# tiny-tinyisp.net
KiCad netlist of a schematic drawn in EAGLE
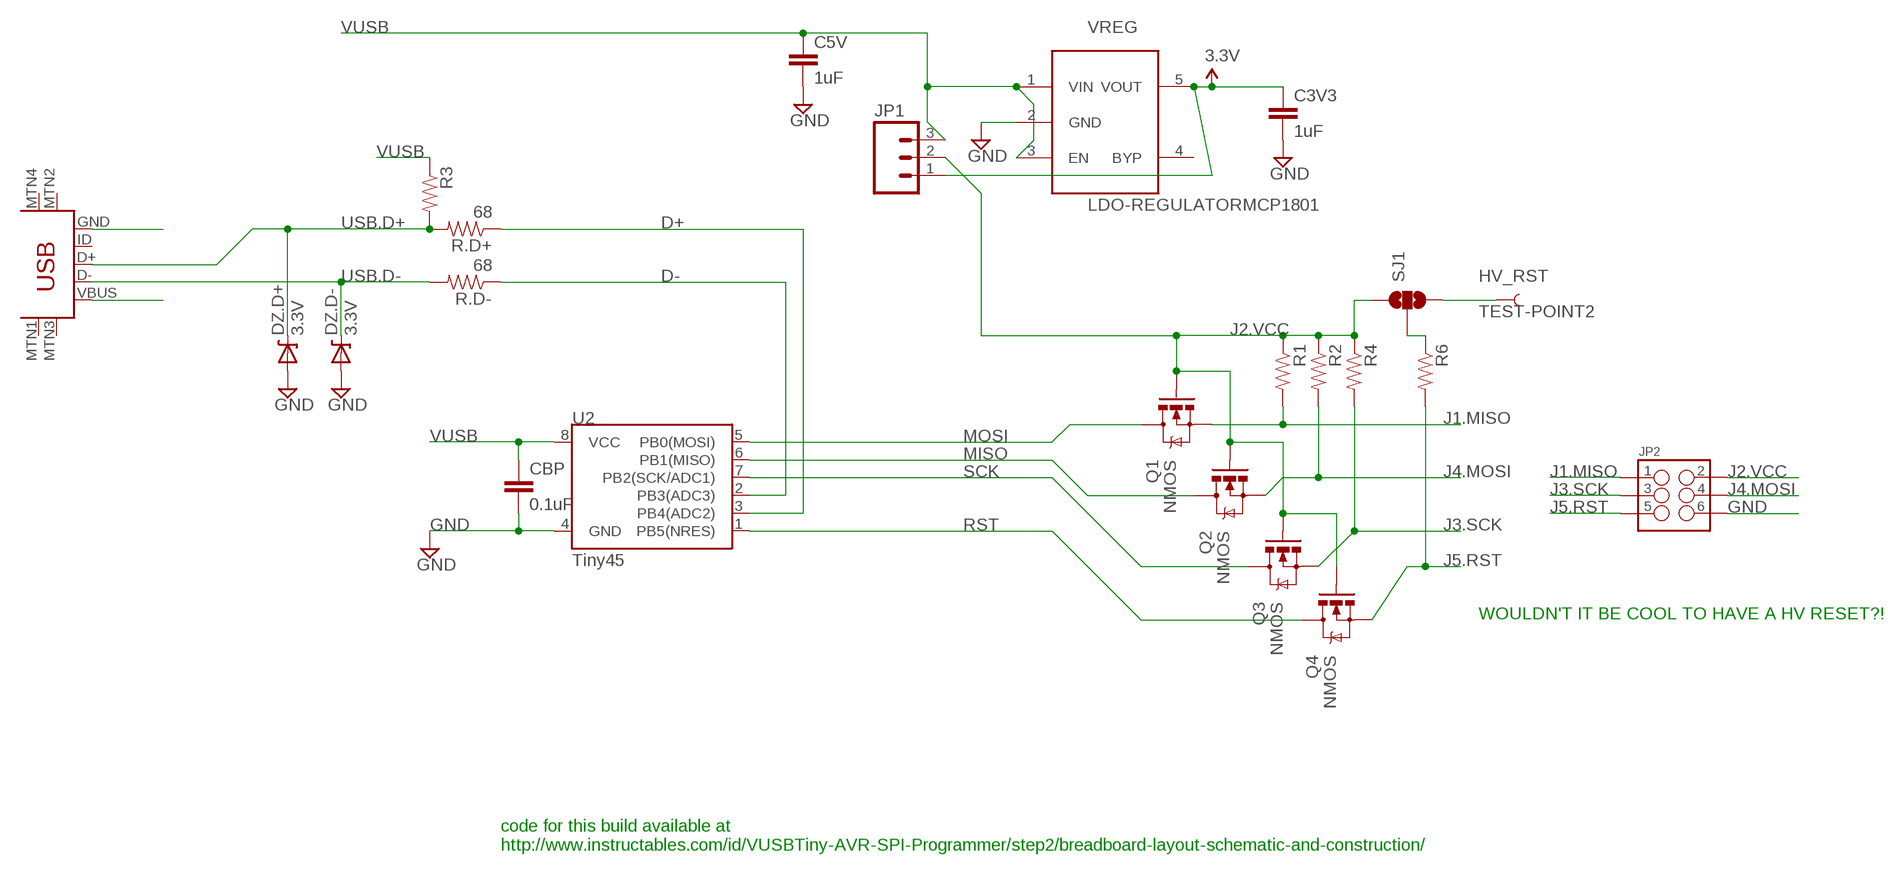
[diagram p0: schematic, sheet 1]

(export (version "E")
  (design (tool "Eeschema 10.0.6"))
  (components
    (comp (ref "C3V3")
      (value "1uF")
      (footprint "eagle-import:0603-CAP")
      (libsource (lib "eagle-import") (part "0.1UF-25V(+80/-20%)(0603)"))
    )
    (comp (ref "C5V")
      (value "1uF")
      (footprint "eagle-import:0603-CAP")
      (libsource (lib "eagle-import") (part "0.1UF-25V(+80/-20%)(0603)"))
    )
    (comp (ref "CBP")
      (value "0.1uF")
      (footprint "eagle-import:0603-CAP")
      (libsource (lib "eagle-import") (part "0.1UF-25V(+80/-20%)(0603)"))
    )
    (comp (ref "DZ.D+")
      (value "3.3V")
      (footprint "eagle-import:SOD-323")
      (libsource (lib "eagle-import") (part "DIODE-ZENER-BZT52"))
    )
    (comp (ref "DZ.D-")
      (value "3.3V")
      (footprint "eagle-import:SOD-323")
      (libsource (lib "eagle-import") (part "DIODE-ZENER-BZT52"))
    )
    (comp (ref "HV_RST")
      (value "TEST-POINT2")
      (footprint "eagle-import:PAD.02X.02")
      (libsource (lib "eagle-import") (part "TEST-POINT2"))
    )
    (comp (ref "JP1")
      (value "M03PTH")
      (footprint "eagle-import:1X03")
      (libsource (lib "eagle-import") (part "M03PTH"))
    )
    (comp (ref "JP2")
      (value "M03X22X3_SILK_SM")
      (footprint "eagle-import:2X3")
      (libsource (lib "eagle-import") (part "M03X22X3_SILK_SM"))
    )
    (comp (ref "Q1")
      (value "NMOS")
      (footprint "eagle-import:SOT323")
      (libsource (lib "eagle-import") (part "MOSFET-NCHANNEL2N7002PW"))
    )
    (comp (ref "Q2")
      (value "NMOS")
      (footprint "eagle-import:SOT323")
      (libsource (lib "eagle-import") (part "MOSFET-NCHANNEL2N7002PW"))
    )
    (comp (ref "Q3")
      (value "NMOS")
      (footprint "eagle-import:SOT323")
      (libsource (lib "eagle-import") (part "MOSFET-NCHANNEL2N7002PW"))
    )
    (comp (ref "Q4")
      (value "NMOS")
      (footprint "eagle-import:SOT323")
      (libsource (lib "eagle-import") (part "MOSFET-NCHANNEL2N7002PW"))
    )
    (comp (ref "R.D+")
      (value "68")
      (footprint "eagle-import:0805")
      (libsource (lib "eagle-import") (part "RESISTOR0805-RES"))
    )
    (comp (ref "R.D-")
      (value "68")
      (footprint "eagle-import:0805")
      (libsource (lib "eagle-import") (part "RESISTOR0805-RES"))
    )
    (comp (ref "R1")
      (value "RESISTOR0805-RES")
      (footprint "eagle-import:0805")
      (libsource (lib "eagle-import") (part "RESISTOR0805-RES"))
    )
    (comp (ref "R2")
      (value "RESISTOR0805-RES")
      (footprint "eagle-import:0805")
      (libsource (lib "eagle-import") (part "RESISTOR0805-RES"))
    )
    (comp (ref "R3")
      (value "RESISTOR0805-RES")
      (footprint "eagle-import:0805")
      (libsource (lib "eagle-import") (part "RESISTOR0805-RES"))
    )
    (comp (ref "R4")
      (value "RESISTOR0805-RES")
      (footprint "eagle-import:0805")
      (libsource (lib "eagle-import") (part "RESISTOR0805-RES"))
    )
    (comp (ref "R6")
      (value "RESISTOR0805-RES")
      (footprint "eagle-import:0805")
      (libsource (lib "eagle-import") (part "RESISTOR0805-RES"))
    )
    (comp (ref "SJ1")
      (value "SOLDERJUMPER_2WAYPASTE1&2")
      (footprint "eagle-import:SJ_3_PASTE1&2")
      (libsource (lib "eagle-import") (part "SOLDERJUMPER_2WAYPASTE1&2"))
    )
    (comp (ref "U$1")
      (value "USB-MINIB")
      (footprint "eagle-import:USB-MINIB")
      (libsource (lib "eagle-import") (part "USB-MINIB-5PIN"))
    )
    (comp (ref "U2")
      (value "Tiny45")
      (footprint "eagle-import:SO08-EIAJ")
      (libsource (lib "eagle-import") (part "ATTINY45TINY45-20-SMT"))
    )
    (comp (ref "VREG")
      (value "LDO-REGULATORMCP1801")
      (footprint "eagle-import:SOT23-5L")
      (libsource (lib "eagle-import") (part "LDO-REGULATORMCP1801"))
    )
  )
  (nets
    (net (code "1") (name "/D+") (class "Default")
      (node (ref "R.D+") (pin "1") (pinfunction "1_1") (pintype "passive"))
      (node (ref "U2") (pin "3") (pinfunction "PB4(ADC2)_3") (pintype "bidirectional"))
    )
    (net (code "2") (name "/D-") (class "Default")
      (node (ref "R.D-") (pin "1") (pinfunction "1_1") (pintype "passive"))
      (node (ref "U2") (pin "2") (pinfunction "PB3(ADC3)_2") (pintype "bidirectional"))
    )
    (net (code "3") (name "/J1.MISO") (class "Default")
      (node (ref "JP2") (pin "1") (pinfunction "1_1") (pintype "bidirectional"))
      (node (ref "Q1") (pin "2") (pinfunction "S_2") (pintype "passive"))
      (node (ref "R1") (pin "2") (pinfunction "2_2") (pintype "passive"))
    )
    (net (code "4") (name "/J2.VCC") (class "Default")
      (node (ref "JP1") (pin "2") (pinfunction "2_2") (pintype "passive"))
      (node (ref "JP2") (pin "2") (pinfunction "2_2") (pintype "bidirectional"))
      (node (ref "Q1") (pin "1") (pinfunction "G_1") (pintype "passive"))
      (node (ref "Q2") (pin "1") (pinfunction "G_1") (pintype "passive"))
      (node (ref "Q3") (pin "1") (pinfunction "G_1") (pintype "passive"))
      (node (ref "Q4") (pin "1") (pinfunction "G_1") (pintype "passive"))
      (node (ref "R1") (pin "1") (pinfunction "1_1") (pintype "passive"))
      (node (ref "R2") (pin "1") (pinfunction "1_1") (pintype "passive"))
      (node (ref "R4") (pin "1") (pinfunction "1_1") (pintype "passive"))
      (node (ref "SJ1") (pin "1") (pinfunction "1_1") (pintype "passive"))
    )
    (net (code "5") (name "/J3.SCK") (class "Default")
      (node (ref "JP2") (pin "3") (pinfunction "3_3") (pintype "bidirectional"))
      (node (ref "Q3") (pin "2") (pinfunction "S_2") (pintype "passive"))
      (node (ref "R4") (pin "2") (pinfunction "2_2") (pintype "passive"))
    )
    (net (code "6") (name "/J4.MOSI") (class "Default")
      (node (ref "JP2") (pin "4") (pinfunction "4_4") (pintype "bidirectional"))
      (node (ref "Q2") (pin "2") (pinfunction "S_2") (pintype "passive"))
      (node (ref "R2") (pin "2") (pinfunction "2_2") (pintype "passive"))
    )
    (net (code "7") (name "/J5.RST") (class "Default")
      (node (ref "JP2") (pin "5") (pinfunction "5_5") (pintype "bidirectional"))
      (node (ref "Q4") (pin "2") (pinfunction "S_2") (pintype "passive"))
      (node (ref "R6") (pin "2") (pinfunction "2_2") (pintype "passive"))
    )
    (net (code "8") (name "/MISO") (class "Default")
      (node (ref "Q2") (pin "3") (pinfunction "D_3") (pintype "passive"))
      (node (ref "U2") (pin "6") (pinfunction "PB1(MISO)_6") (pintype "bidirectional"))
    )
    (net (code "9") (name "/MOSI") (class "Default")
      (node (ref "Q1") (pin "3") (pinfunction "D_3") (pintype "passive"))
      (node (ref "U2") (pin "5") (pinfunction "PB0(MOSI)_5") (pintype "bidirectional"))
    )
    (net (code "10") (name "/RST") (class "Default")
      (node (ref "Q4") (pin "3") (pinfunction "D_3") (pintype "passive"))
      (node (ref "U2") (pin "1") (pinfunction "PB5(NRES)_1") (pintype "bidirectional"))
    )
    (net (code "11") (name "/SCK") (class "Default")
      (node (ref "Q3") (pin "3") (pinfunction "D_3") (pintype "passive"))
      (node (ref "U2") (pin "7") (pinfunction "PB2(SCK/ADC1)_7") (pintype "bidirectional"))
    )
    (net (code "12") (name "/USB.D+") (class "Default")
      (node (ref "DZ.D+") (pin "1") (pinfunction "C_1") (pintype "passive"))
      (node (ref "R.D+") (pin "2") (pinfunction "2_2") (pintype "passive"))
      (node (ref "R3") (pin "2") (pinfunction "2_2") (pintype "passive"))
      (node (ref "U$1") (pin "D+") (pinfunction "D+_D+") (pintype "bidirectional"))
    )
    (net (code "13") (name "/USB.D-") (class "Default")
      (node (ref "DZ.D-") (pin "1") (pinfunction "C_1") (pintype "passive"))
      (node (ref "R.D-") (pin "2") (pinfunction "2_2") (pintype "passive"))
      (node (ref "U$1") (pin "D-") (pinfunction "D-_D-") (pintype "bidirectional"))
    )
    (net (code "14") (name "/VUSB") (class "Default")
      (node (ref "C5V") (pin "1") (pinfunction "1_1") (pintype "passive"))
      (node (ref "CBP") (pin "1") (pinfunction "1_1") (pintype "passive"))
      (node (ref "JP1") (pin "3") (pinfunction "3_3") (pintype "passive"))
      (node (ref "R3") (pin "1") (pinfunction "1_1") (pintype "passive"))
      (node (ref "U$1") (pin "VBUS") (pinfunction "VBUS_VBUS") (pintype "bidirectional"))
      (node (ref "U2") (pin "8") (pinfunction "VCC_8") (pintype "bidirectional"))
      (node (ref "VREG") (pin "1") (pinfunction "VIN_1") (pintype "bidirectional"))
      (node (ref "VREG") (pin "3") (pinfunction "EN_3") (pintype "bidirectional"))
    )
    (net (code "15") (name "3.3V") (class "Default")
      (node (ref "C3V3") (pin "1") (pinfunction "1_1") (pintype "passive"))
      (node (ref "JP1") (pin "1") (pinfunction "1_1") (pintype "passive"))
      (node (ref "VREG") (pin "5") (pinfunction "VOUT_5") (pintype "bidirectional"))
    )
    (net (code "16") (name "GND") (class "Default")
      (node (ref "C3V3") (pin "2") (pinfunction "2_2") (pintype "passive"))
      (node (ref "C5V") (pin "2") (pinfunction "2_2") (pintype "passive"))
      (node (ref "CBP") (pin "2") (pinfunction "2_2") (pintype "passive"))
      (node (ref "DZ.D+") (pin "2") (pinfunction "A_2") (pintype "passive"))
      (node (ref "DZ.D-") (pin "2") (pinfunction "A_2") (pintype "passive"))
      (node (ref "JP2") (pin "6") (pinfunction "6_6") (pintype "bidirectional"))
      (node (ref "U$1") (pin "GND") (pinfunction "GND_GND") (pintype "bidirectional"))
      (node (ref "U2") (pin "4") (pinfunction "GND_4") (pintype "bidirectional"))
      (node (ref "VREG") (pin "2") (pinfunction "GND_2") (pintype "bidirectional"))
    )
    (net (code "17") (name "Net-(HV_RST-1)") (class "Default")
      (node (ref "HV_RST") (pin "P$1") (pinfunction "1_P$1") (pintype "bidirectional"))
      (node (ref "SJ1") (pin "3") (pinfunction "3_3") (pintype "passive"))
    )
    (net (code "18") (name "Net-(R6-Pad1)") (class "Default")
      (node (ref "R6") (pin "1") (pinfunction "1_1") (pintype "passive"))
      (node (ref "SJ1") (pin "2") (pinfunction "2_2") (pintype "passive"))
    )
    (net (code "19") (name "unconnected-(U$1-MTN1-PadMTN3)") (class "Default")
      (node (ref "U$1") (pin "MTN3") (pinfunction "MTN1_MTN3") (pintype "bidirectional"))
    )
    (net (code "20") (name "unconnected-(U$1-MTN2-PadMTN1)") (class "Default")
      (node (ref "U$1") (pin "MTN1") (pinfunction "MTN2_MTN1") (pintype "bidirectional"))
    )
    (net (code "21") (name "unconnected-(U$1-MTN3-PadMTN2)") (class "Default")
      (node (ref "U$1") (pin "MTN2") (pinfunction "MTN3_MTN2") (pintype "bidirectional"))
    )
    (net (code "22") (name "unconnected-(U$1-PadID)") (class "Default")
      (node (ref "U$1") (pin "ID") (pinfunction "ID_ID") (pintype "bidirectional"))
    )
    (net (code "23") (name "unconnected-(U$1-PadMTN4)") (class "Default")
      (node (ref "U$1") (pin "MTN4") (pinfunction "MTN4_MTN4") (pintype "bidirectional"))
    )
    (net (code "24") (name "unconnected-(VREG-BYP-Pad4)") (class "Default")
      (node (ref "VREG") (pin "4") (pinfunction "BYP_4") (pintype "bidirectional"))
    )
  )
)
